# Electron_Qwiic.net
KiCad netlist of a schematic drawn in EAGLE
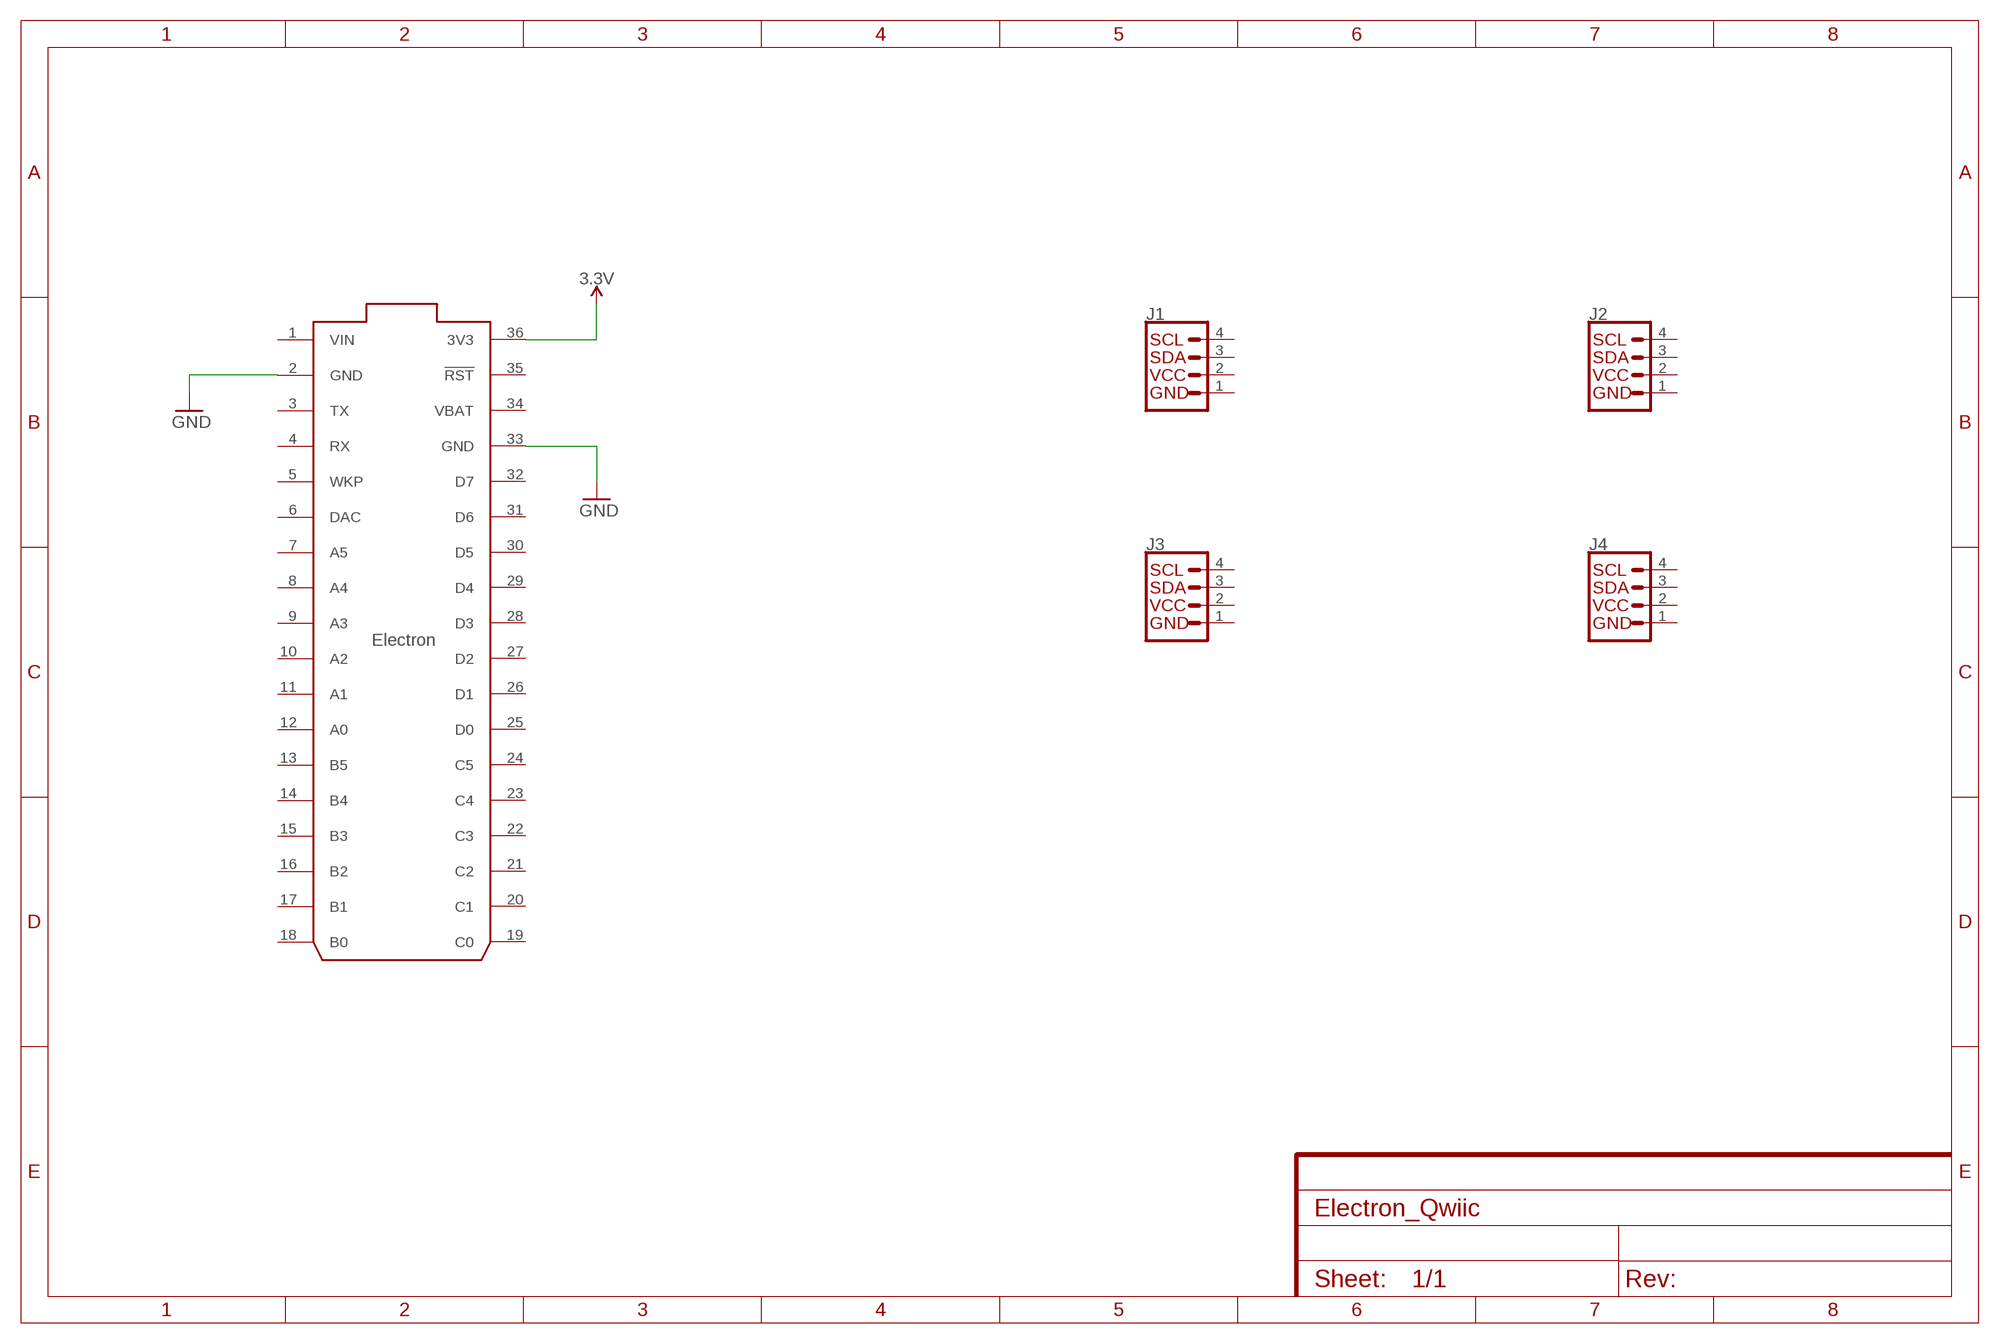
[diagram p0: schematic, sheet 1]

(export (version "E")
  (design (tool "Eeschema 10.0.6"))
  (components
    (comp (ref "J1")
      (value "QWIIC_CONNECTORJS-1MM")
      (footprint "eagle-import:1X04_1MM_RA")
      (libsource (lib "eagle-import") (part "QWIIC_CONNECTORJS-1MM"))
    )
    (comp (ref "J2")
      (value "QWIIC_CONNECTORJS-1MM")
      (footprint "eagle-import:1X04_1MM_RA")
      (libsource (lib "eagle-import") (part "QWIIC_CONNECTORJS-1MM"))
    )
    (comp (ref "J3")
      (value "QWIIC_CONNECTORJS-1MM")
      (footprint "eagle-import:1X04_1MM_RA")
      (libsource (lib "eagle-import") (part "QWIIC_CONNECTORJS-1MM"))
    )
    (comp (ref "J4")
      (value "QWIIC_CONNECTORJS-1MM")
      (footprint "eagle-import:1X04_1MM_RA")
      (libsource (lib "eagle-import") (part "QWIIC_CONNECTORJS-1MM"))
    )
    (comp (ref "U$1")
      (value "ELECTRON_WITH_HEADERS")
      (footprint "eagle-import:ELECTRON")
      (libsource (lib "eagle-import") (part "ELECTRON_WITH_HEADERS"))
    )
  )
  (nets
    (net (code "1") (name "/VBAT") (class "Default")
      (node (ref "U$1") (pin "34") (pinfunction "VBAT_34") (pintype "power_in"))
    )
    (net (code "2") (name "/VIN") (class "Default")
      (node (ref "U$1") (pin "1") (pinfunction "VIN_1") (pintype "power_in"))
    )
    (net (code "3") (name "3.3V") (class "Default")
      (node (ref "U$1") (pin "36") (pinfunction "3V3_36") (pintype "power_in"))
    )
    (net (code "4") (name "GND") (class "Default")
      (node (ref "U$1") (pin "2") (pinfunction "GND_2") (pintype "power_in"))
      (node (ref "U$1") (pin "33") (pinfunction "GND_33") (pintype "power_in"))
    )
    (net (code "5") (name "unconnected-(J1-GND-Pad1)") (class "Default")
      (node (ref "J1") (pin "1") (pinfunction "GND_1") (pintype "power_in"))
    )
    (net (code "6") (name "unconnected-(J1-SCL-Pad4)") (class "Default")
      (node (ref "J1") (pin "4") (pinfunction "SCL_4") (pintype "passive"))
    )
    (net (code "7") (name "unconnected-(J1-SDA-Pad3)") (class "Default")
      (node (ref "J1") (pin "3") (pinfunction "SDA_3") (pintype "passive"))
    )
    (net (code "8") (name "unconnected-(J1-VCC-Pad2)") (class "Default")
      (node (ref "J1") (pin "2") (pinfunction "VCC_2") (pintype "power_in"))
    )
    (net (code "9") (name "unconnected-(J2-GND-Pad1)") (class "Default")
      (node (ref "J2") (pin "1") (pinfunction "GND_1") (pintype "power_in"))
    )
    (net (code "10") (name "unconnected-(J2-SCL-Pad4)") (class "Default")
      (node (ref "J2") (pin "4") (pinfunction "SCL_4") (pintype "passive"))
    )
    (net (code "11") (name "unconnected-(J2-SDA-Pad3)") (class "Default")
      (node (ref "J2") (pin "3") (pinfunction "SDA_3") (pintype "passive"))
    )
    (net (code "12") (name "unconnected-(J2-VCC-Pad2)") (class "Default")
      (node (ref "J2") (pin "2") (pinfunction "VCC_2") (pintype "power_in"))
    )
    (net (code "13") (name "unconnected-(J3-GND-Pad1)") (class "Default")
      (node (ref "J3") (pin "1") (pinfunction "GND_1") (pintype "power_in"))
    )
    (net (code "14") (name "unconnected-(J3-SCL-Pad4)") (class "Default")
      (node (ref "J3") (pin "4") (pinfunction "SCL_4") (pintype "passive"))
    )
    (net (code "15") (name "unconnected-(J3-SDA-Pad3)") (class "Default")
      (node (ref "J3") (pin "3") (pinfunction "SDA_3") (pintype "passive"))
    )
    (net (code "16") (name "unconnected-(J3-VCC-Pad2)") (class "Default")
      (node (ref "J3") (pin "2") (pinfunction "VCC_2") (pintype "power_in"))
    )
    (net (code "17") (name "unconnected-(J4-GND-Pad1)") (class "Default")
      (node (ref "J4") (pin "1") (pinfunction "GND_1") (pintype "power_in"))
    )
    (net (code "18") (name "unconnected-(J4-SCL-Pad4)") (class "Default")
      (node (ref "J4") (pin "4") (pinfunction "SCL_4") (pintype "passive"))
    )
    (net (code "19") (name "unconnected-(J4-SDA-Pad3)") (class "Default")
      (node (ref "J4") (pin "3") (pinfunction "SDA_3") (pintype "passive"))
    )
    (net (code "20") (name "unconnected-(J4-VCC-Pad2)") (class "Default")
      (node (ref "J4") (pin "2") (pinfunction "VCC_2") (pintype "power_in"))
    )
    (net (code "21") (name "unconnected-(U$1-A0-Pad12)") (class "Default")
      (node (ref "U$1") (pin "12") (pinfunction "A0_12") (pintype "bidirectional"))
    )
    (net (code "22") (name "unconnected-(U$1-A1-Pad11)") (class "Default")
      (node (ref "U$1") (pin "11") (pinfunction "A1_11") (pintype "bidirectional"))
    )
    (net (code "23") (name "unconnected-(U$1-A2-Pad10)") (class "Default")
      (node (ref "U$1") (pin "10") (pinfunction "A2_10") (pintype "bidirectional"))
    )
    (net (code "24") (name "unconnected-(U$1-A3-Pad9)") (class "Default")
      (node (ref "U$1") (pin "9") (pinfunction "A3_9") (pintype "bidirectional"))
    )
    (net (code "25") (name "unconnected-(U$1-A4-Pad8)") (class "Default")
      (node (ref "U$1") (pin "8") (pinfunction "A4_8") (pintype "bidirectional"))
    )
    (net (code "26") (name "unconnected-(U$1-A5-Pad7)") (class "Default")
      (node (ref "U$1") (pin "7") (pinfunction "A5_7") (pintype "bidirectional"))
    )
    (net (code "27") (name "unconnected-(U$1-B0-Pad18)") (class "Default")
      (node (ref "U$1") (pin "18") (pinfunction "B0_18") (pintype "bidirectional"))
    )
    (net (code "28") (name "unconnected-(U$1-B1-Pad17)") (class "Default")
      (node (ref "U$1") (pin "17") (pinfunction "B1_17") (pintype "bidirectional"))
    )
    (net (code "29") (name "unconnected-(U$1-B2-Pad16)") (class "Default")
      (node (ref "U$1") (pin "16") (pinfunction "B2_16") (pintype "bidirectional"))
    )
    (net (code "30") (name "unconnected-(U$1-B3-Pad15)") (class "Default")
      (node (ref "U$1") (pin "15") (pinfunction "B3_15") (pintype "bidirectional"))
    )
    (net (code "31") (name "unconnected-(U$1-B4-Pad14)") (class "Default")
      (node (ref "U$1") (pin "14") (pinfunction "B4_14") (pintype "bidirectional"))
    )
    (net (code "32") (name "unconnected-(U$1-B5-Pad13)") (class "Default")
      (node (ref "U$1") (pin "13") (pinfunction "B5_13") (pintype "bidirectional"))
    )
    (net (code "33") (name "unconnected-(U$1-C0-Pad19)") (class "Default")
      (node (ref "U$1") (pin "19") (pinfunction "C0_19") (pintype "bidirectional"))
    )
    (net (code "34") (name "unconnected-(U$1-C1-Pad20)") (class "Default")
      (node (ref "U$1") (pin "20") (pinfunction "C1_20") (pintype "bidirectional"))
    )
    (net (code "35") (name "unconnected-(U$1-C2-Pad21)") (class "Default")
      (node (ref "U$1") (pin "21") (pinfunction "C2_21") (pintype "bidirectional"))
    )
    (net (code "36") (name "unconnected-(U$1-C3-Pad22)") (class "Default")
      (node (ref "U$1") (pin "22") (pinfunction "C3_22") (pintype "bidirectional"))
    )
    (net (code "37") (name "unconnected-(U$1-C4-Pad23)") (class "Default")
      (node (ref "U$1") (pin "23") (pinfunction "C4_23") (pintype "bidirectional"))
    )
    (net (code "38") (name "unconnected-(U$1-C5-Pad24)") (class "Default")
      (node (ref "U$1") (pin "24") (pinfunction "C5_24") (pintype "bidirectional"))
    )
    (net (code "39") (name "unconnected-(U$1-D0-Pad25)") (class "Default")
      (node (ref "U$1") (pin "25") (pinfunction "D0_25") (pintype "bidirectional"))
    )
    (net (code "40") (name "unconnected-(U$1-D1-Pad26)") (class "Default")
      (node (ref "U$1") (pin "26") (pinfunction "D1_26") (pintype "bidirectional"))
    )
    (net (code "41") (name "unconnected-(U$1-D2-Pad27)") (class "Default")
      (node (ref "U$1") (pin "27") (pinfunction "D2_27") (pintype "bidirectional"))
    )
    (net (code "42") (name "unconnected-(U$1-D3-Pad28)") (class "Default")
      (node (ref "U$1") (pin "28") (pinfunction "D3_28") (pintype "bidirectional"))
    )
    (net (code "43") (name "unconnected-(U$1-D4-Pad29)") (class "Default")
      (node (ref "U$1") (pin "29") (pinfunction "D4_29") (pintype "bidirectional"))
    )
    (net (code "44") (name "unconnected-(U$1-D5-Pad30)") (class "Default")
      (node (ref "U$1") (pin "30") (pinfunction "D5_30") (pintype "bidirectional"))
    )
    (net (code "45") (name "unconnected-(U$1-D6-Pad31)") (class "Default")
      (node (ref "U$1") (pin "31") (pinfunction "D6_31") (pintype "bidirectional"))
    )
    (net (code "46") (name "unconnected-(U$1-D7-Pad32)") (class "Default")
      (node (ref "U$1") (pin "32") (pinfunction "D7_32") (pintype "bidirectional"))
    )
    (net (code "47") (name "unconnected-(U$1-DAC-Pad6)") (class "Default")
      (node (ref "U$1") (pin "6") (pinfunction "DAC_6") (pintype "bidirectional"))
    )
    (net (code "48") (name "unconnected-(U$1-RX-Pad4)") (class "Default")
      (node (ref "U$1") (pin "4") (pinfunction "RX_4") (pintype "bidirectional"))
    )
    (net (code "49") (name "unconnected-(U$1-TX-Pad3)") (class "Default")
      (node (ref "U$1") (pin "3") (pinfunction "TX_3") (pintype "bidirectional"))
    )
    (net (code "50") (name "unconnected-(U$1-WKP-Pad5)") (class "Default")
      (node (ref "U$1") (pin "5") (pinfunction "WKP_5") (pintype "bidirectional"))
    )
    (net (code "51") (name "unconnected-(U$1-~{RST}-Pad35)") (class "Default")
      (node (ref "U$1") (pin "35") (pinfunction "~{RST}_35") (pintype "bidirectional"))
    )
  )
)
